# Pilot_Tone_-_Reference.net
KiCad netlist of a schematic drawn in Altium Designer
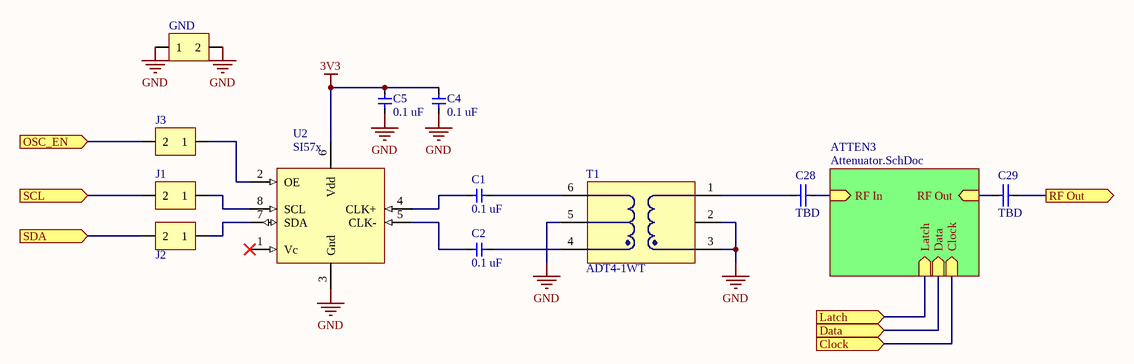
[diagram p0: Pilot Tone - Reference.SchDoc]

(export (version "E")
  (design (tool "Eeschema 10.0.6"))
  (components
    (comp (ref "C1")
      (value "0.1 uF")
      (footprint "0603C")
      (description "SMT Cap")
      (fields (field (name "PUBLISHER") "Altium Limited"))
      (libsource (lib "Miscellaneous Devices") (part "Cap - SMT Small"))
    )
    (comp (ref "C2")
      (value "0.1 uF")
      (footprint "0603C")
      (description "SMT Cap")
      (fields (field (name "PUBLISHER") "Altium Limited"))
      (libsource (lib "Miscellaneous Devices") (part "Cap - SMT Small"))
    )
    (comp (ref "C4")
      (value "0.1 uF")
      (footprint "0603C")
      (description "SMT Cap")
      (fields (field (name "PUBLISHER") "Altium Limited"))
      (libsource (lib "Miscellaneous Devices") (part "Cap - SMT Small"))
    )
    (comp (ref "C5")
      (value "0.1 uF")
      (footprint "0603C")
      (description "SMT Cap")
      (fields (field (name "PUBLISHER") "Altium Limited"))
      (libsource (lib "Miscellaneous Devices") (part "Cap - SMT Small"))
    )
    (comp (ref "C28")
      (value "TBD")
      (footprint "0402C")
      (description "Capacitor")
      (fields (field (name "Comment") "Cap") (field (name "PUBLISHER") "Altium Limited"))
      (libsource (lib "Miscellaneous Devices") (part "Cap"))
    )
    (comp (ref "C29")
      (value "TBD")
      (footprint "0402C")
      (description "Capacitor")
      (fields (field (name "Comment") "Cap") (field (name "PUBLISHER") "Altium Limited"))
      (libsource (lib "Miscellaneous Devices") (part "Cap"))
    )
    (comp (ref "GND")
      (value "Jumper")
      (footprint "HDR1X2")
      (description "Jumper - 2-Pin")
      (fields (field (name "PUBLISHER") "Altium Limited"))
      (libsource (lib "") (part "Jumper - 2 Pin_1"))
    )
    (comp (ref "J1")
      (value "Jumper")
      (footprint "0603R")
      (description "Jumper - 2-Pin")
      (fields (field (name "PUBLISHER") "Altium Limited"))
      (libsource (lib "Miscellaneous Connectors") (part "Jumper - 2 Pin"))
    )
    (comp (ref "J2")
      (value "Jumper")
      (footprint "0603R")
      (description "Jumper - 2-Pin")
      (fields (field (name "PUBLISHER") "Altium Limited"))
      (libsource (lib "Miscellaneous Connectors") (part "Jumper - 2 Pin"))
    )
    (comp (ref "J3")
      (value "Jumper")
      (footprint "0603R")
      (description "Jumper - 2-Pin")
      (fields (field (name "PUBLISHER") "Altium Limited"))
      (libsource (lib "Miscellaneous Connectors") (part "Jumper - 2 Pin"))
    )
    (comp (ref "T1")
      (value "ADT4-1WT")
      (footprint "CD542")
      (description "Surface Mount RF Transformer")
      (libsource (lib "RF Components") (part "ADT4-1WT"))
    )
    (comp (ref "U2")
      (value "SI57x")
      (footprint "SI57x")
      (description "10 MHZ TO 1.4 GHZ I2C PROGRAMMABLE XO/VCXO")
      (libsource (lib "RF Components") (part "SI570"))
    )
  )
  (nets
    (net (code "4") (name "/OSC_EN") (class "Default")
      (node (ref "J3") (pin "2") (pinfunction "2_2") (pintype "passive"))
    )
    (net (code "5") (name "/RF In") (class "Default")
      (node (ref "C28") (pin "2") (pinfunction "2_2") (pintype "passive"))
    )
    (net (code "6") (name "/RF Out") (class "Default")
      (node (ref "C29") (pin "2") (pinfunction "2_2") (pintype "passive"))
    )
    (net (code "7") (name "/RF Out_1") (class "Default")
      (node (ref "C29") (pin "1") (pinfunction "1_1") (pintype "passive"))
    )
    (net (code "8") (name "/SCL") (class "Default")
      (node (ref "J1") (pin "2") (pinfunction "2_2") (pintype "passive"))
    )
    (net (code "9") (name "/SDA") (class "Default")
      (node (ref "J2") (pin "2") (pinfunction "2_2") (pintype "passive"))
    )
    (net (code "10") (name "3V3") (class "Default")
      (node (ref "C4") (pin "2") (pinfunction "2_2") (pintype "passive"))
      (node (ref "C5") (pin "2") (pinfunction "2_2") (pintype "passive"))
      (node (ref "U2") (pin "6") (pinfunction "Vdd_6") (pintype "power_in"))
    )
    (net (code "11") (name "GND") (class "Default")
      (node (ref "C4") (pin "1") (pinfunction "1_1") (pintype "passive"))
      (node (ref "C5") (pin "1") (pinfunction "1_1") (pintype "passive"))
      (node (ref "GND") (pin "1") (pinfunction "1_1") (pintype "passive"))
      (node (ref "GND") (pin "2") (pinfunction "2_2") (pintype "passive"))
      (node (ref "T1") (pin "2") (pinfunction "Gnd_2") (pintype "power_in"))
      (node (ref "T1") (pin "3") (pinfunction "Coupled_3") (pintype "passive"))
      (node (ref "T1") (pin "5") (pinfunction "Termination_5") (pintype "passive"))
      (node (ref "U2") (pin "3") (pinfunction "Gnd_3") (pintype "power_in"))
    )
    (net (code "12") (name "Net-(C2-Pad2)") (class "Default")
      (node (ref "C2") (pin "2") (pinfunction "2_2") (pintype "passive"))
      (node (ref "T1") (pin "4") (pinfunction "Termination_4") (pintype "passive"))
    )
    (net (code "13") (name "Net-(T1-Input)") (class "Default")
      (node (ref "C28") (pin "1") (pinfunction "1_1") (pintype "passive"))
      (node (ref "T1") (pin "1") (pinfunction "Input_1") (pintype "passive"))
    )
    (net (code "14") (name "Net-(T1-Output)") (class "Default")
      (node (ref "C1") (pin "2") (pinfunction "2_2") (pintype "passive"))
      (node (ref "T1") (pin "6") (pinfunction "Output_6") (pintype "passive"))
    )
    (net (code "15") (name "Net-(U2-CLK+)") (class "Default")
      (node (ref "C1") (pin "1") (pinfunction "1_1") (pintype "passive"))
      (node (ref "U2") (pin "4") (pinfunction "CLK+_4") (pintype "input"))
    )
    (net (code "16") (name "Net-(U2-CLK-)") (class "Default")
      (node (ref "C2") (pin "1") (pinfunction "1_1") (pintype "passive"))
      (node (ref "U2") (pin "5") (pinfunction "CLK-_5") (pintype "input"))
    )
    (net (code "17") (name "Net-(U2-OE)") (class "Default")
      (node (ref "J3") (pin "1") (pinfunction "1_1") (pintype "passive"))
      (node (ref "U2") (pin "2") (pinfunction "OE_2") (pintype "input"))
    )
    (net (code "18") (name "Net-(U2-SCL)") (class "Default")
      (node (ref "J1") (pin "1") (pinfunction "1_1") (pintype "passive"))
      (node (ref "U2") (pin "8") (pinfunction "SCL_8") (pintype "input"))
    )
    (net (code "19") (name "Net-(U2-SDA)") (class "Default")
      (node (ref "J2") (pin "1") (pinfunction "1_1") (pintype "passive"))
      (node (ref "U2") (pin "7") (pinfunction "SDA_7") (pintype "bidirectional"))
    )
    (net (code "20") (name "unconnected-(U2-Vc-Pad1)") (class "Default")
      (node (ref "U2") (pin "1") (pinfunction "Vc_1") (pintype "input+no_connect"))
    )
  )
)
